# 03_Main.net
KiCad netlist of a schematic drawn in Altium Designer
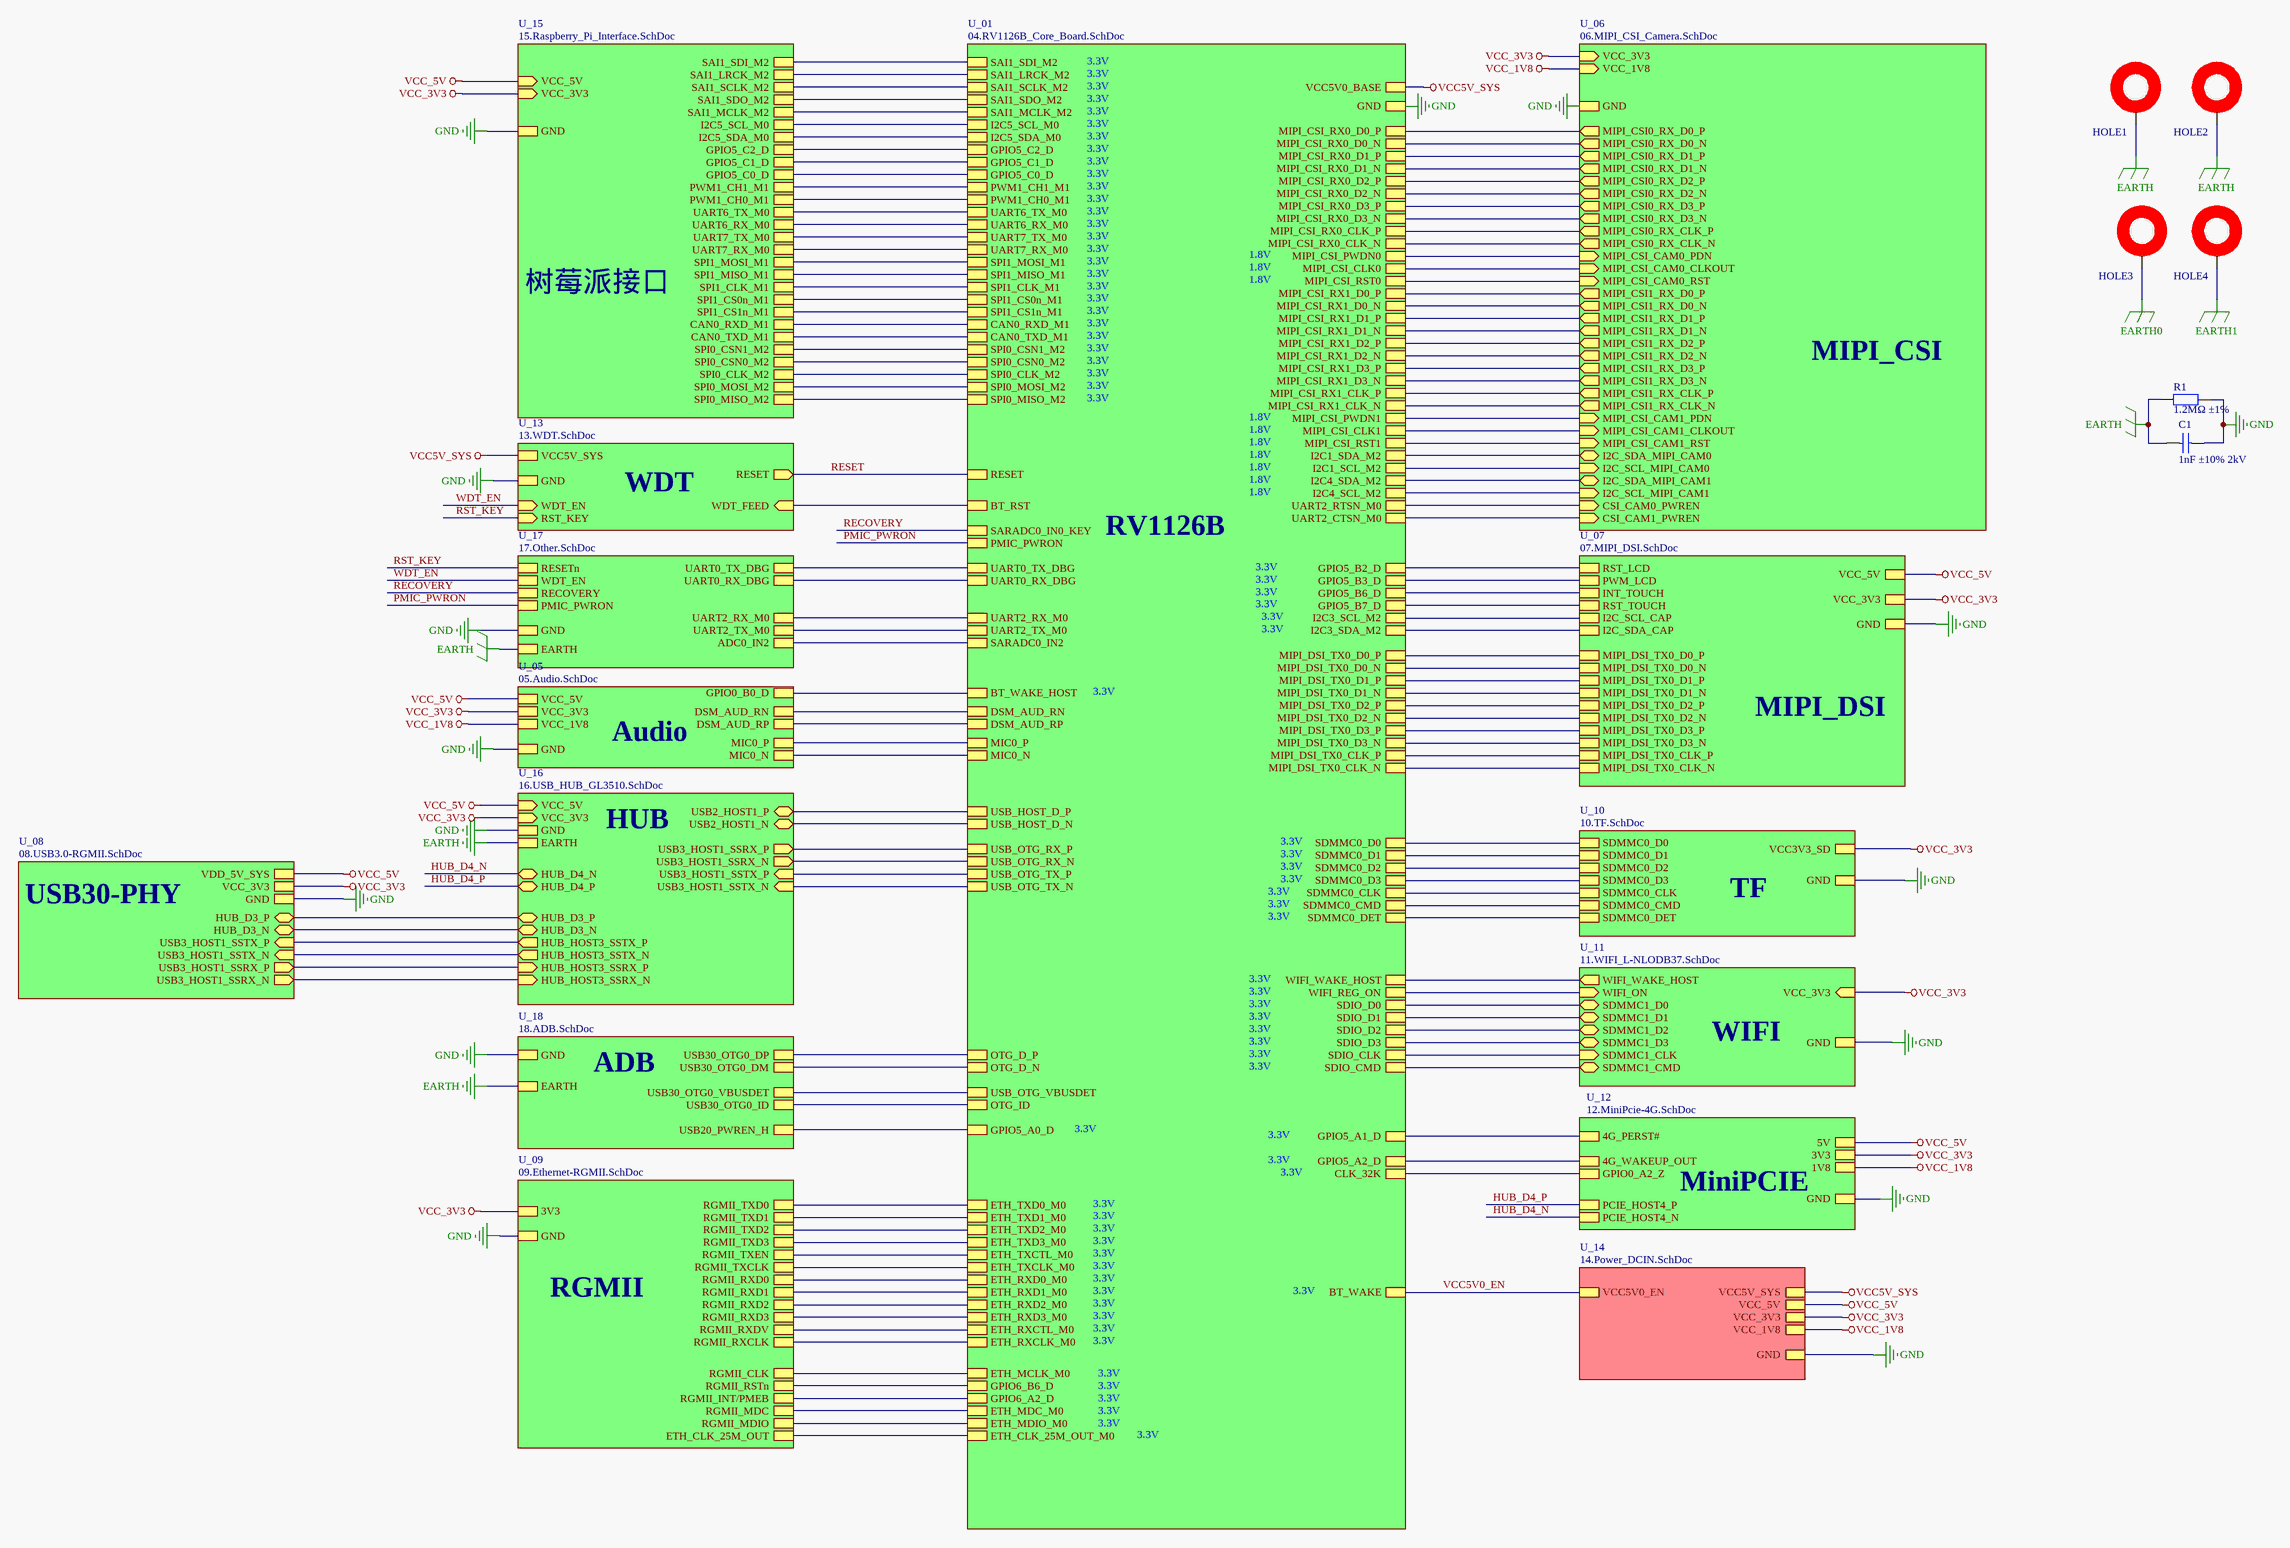
[diagram p0: 03.Main.SchDoc]

(export (version "E")
  (design (tool "Eeschema 10.0.6"))
  (components
    (comp (ref "C1")
      (value "CC1206KKX7RDBB102")
      (footprint "1206_C")
      (description "SPZL000332")
      (fields (field (name "描述") "1nF ±10% 2kV"))
      (libsource (lib "CAP_EASY-EAI") (part "1206 1nF ±10% 2kV"))
    )
    (comp (ref "HOLE1")
      (value "HOLE1")
      (footprint "HOLE-3.2 - Screw")
      (libsource (lib "lib_lexing") (part "HOLE1"))
    )
    (comp (ref "HOLE2")
      (value "HOLE1")
      (footprint "HOLE-3.2 - Screw")
      (libsource (lib "lib_lexing") (part "HOLE1"))
    )
    (comp (ref "HOLE3")
      (value "HOLE1")
      (footprint "HOLE-3.2 - Screw")
      (libsource (lib "lib_lexing") (part "HOLE1"))
    )
    (comp (ref "HOLE4")
      (value "HOLE1")
      (footprint "HOLE-3.2 - Screw")
      (libsource (lib "lib_lexing") (part "HOLE1"))
    )
    (comp (ref "R1")
      (value "1206W4F1204T5E")
      (footprint "1206_R")
      (description "SPZL000388")
      (fields (field (name "描述") "1.2MΩ ±1%"))
      (libsource (lib "RES_EASY-EAI") (part "1206 1.2MΩ ±1%"))
    )
  )
  (nets
    (net (code "149") (name "EARTH") (class "Default")
      (node (ref "C1") (pin "1") (pinfunction "1_1") (pintype "passive"))
      (node (ref "HOLE1") (pin "1") (pintype "passive"))
      (node (ref "HOLE2") (pin "1") (pintype "passive"))
      (node (ref "R1") (pin "1") (pinfunction "1_1") (pintype "passive"))
    )
    (net (code "150") (name "EARTH0") (class "Default") (node (ref "HOLE3") (pin "1") (pintype "passive")))
    (net (code "151") (name "EARTH1") (class "Default") (node (ref "HOLE4") (pin "1") (pintype "passive")))
    (net (code "152") (name "GND") (class "Default")
      (node (ref "C1") (pin "2") (pinfunction "2_2") (pintype "passive"))
      (node (ref "R1") (pin "2") (pinfunction "2_2") (pintype "passive"))
    )
  )
)
